# c.net
KiCad netlist of a schematic drawn in EAGLE
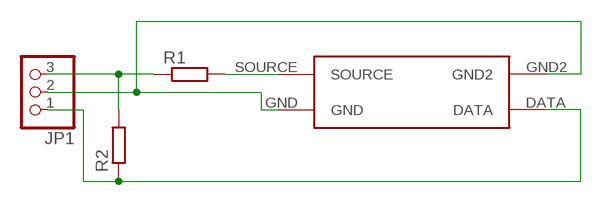
[diagram p0: schematic, sheet 1]

(export (version "E")
  (design (tool "Eeschema 10.0.6"))
  (components
    (comp (ref "JP1")
      (value "PINHD-1X3")
      (footprint "eagle-import:1X03")
      (libsource (lib "eagle-import") (part "PINHD-1X3"))
    )
    (comp (ref "R1")
      (value "R-EU_M1206")
      (footprint "eagle-import:M1206")
      (libsource (lib "eagle-import") (part "R-EU_M1206"))
    )
    (comp (ref "R2")
      (value "R-EU_M1206")
      (footprint "eagle-import:M1206")
      (libsource (lib "eagle-import") (part "R-EU_M1206"))
    )
    (comp (ref "U$1")
      (value "GP2S24")
      (footprint "eagle-import:GP2S24")
      (libsource (lib "eagle-import") (part "GP2S24"))
    )
  )
  (nets
    (net (code "1") (name "Net-(JP1-Pad1)") (class "Default")
      (node (ref "JP1") (pin "1") (pinfunction "1_1") (pintype "passive"))
      (node (ref "R2") (pin "1") (pinfunction "1_1") (pintype "passive"))
      (node (ref "U$1") (pin "DATA") (pinfunction "DATA_DATA") (pintype "bidirectional"))
    )
    (net (code "2") (name "Net-(JP1-Pad2)") (class "Default")
      (node (ref "JP1") (pin "2") (pinfunction "2_2") (pintype "passive"))
      (node (ref "U$1") (pin "GND") (pinfunction "GND_GND") (pintype "bidirectional"))
      (node (ref "U$1") (pin "GND2") (pinfunction "GND2_GND2") (pintype "bidirectional"))
    )
    (net (code "3") (name "Net-(JP1-Pad3)") (class "Default")
      (node (ref "JP1") (pin "3") (pinfunction "3_3") (pintype "passive"))
      (node (ref "R1") (pin "1") (pinfunction "1_1") (pintype "passive"))
      (node (ref "R2") (pin "2") (pinfunction "2_2") (pintype "passive"))
    )
    (net (code "4") (name "Net-(R1-Pad2)") (class "Default")
      (node (ref "R1") (pin "2") (pinfunction "2_2") (pintype "passive"))
      (node (ref "U$1") (pin "SOURCE") (pinfunction "SOURCE_SOURCE") (pintype "bidirectional"))
    )
  )
)
